# 1ChAmp_circuit_Large.net
KiCad netlist of a schematic drawn in EAGLE
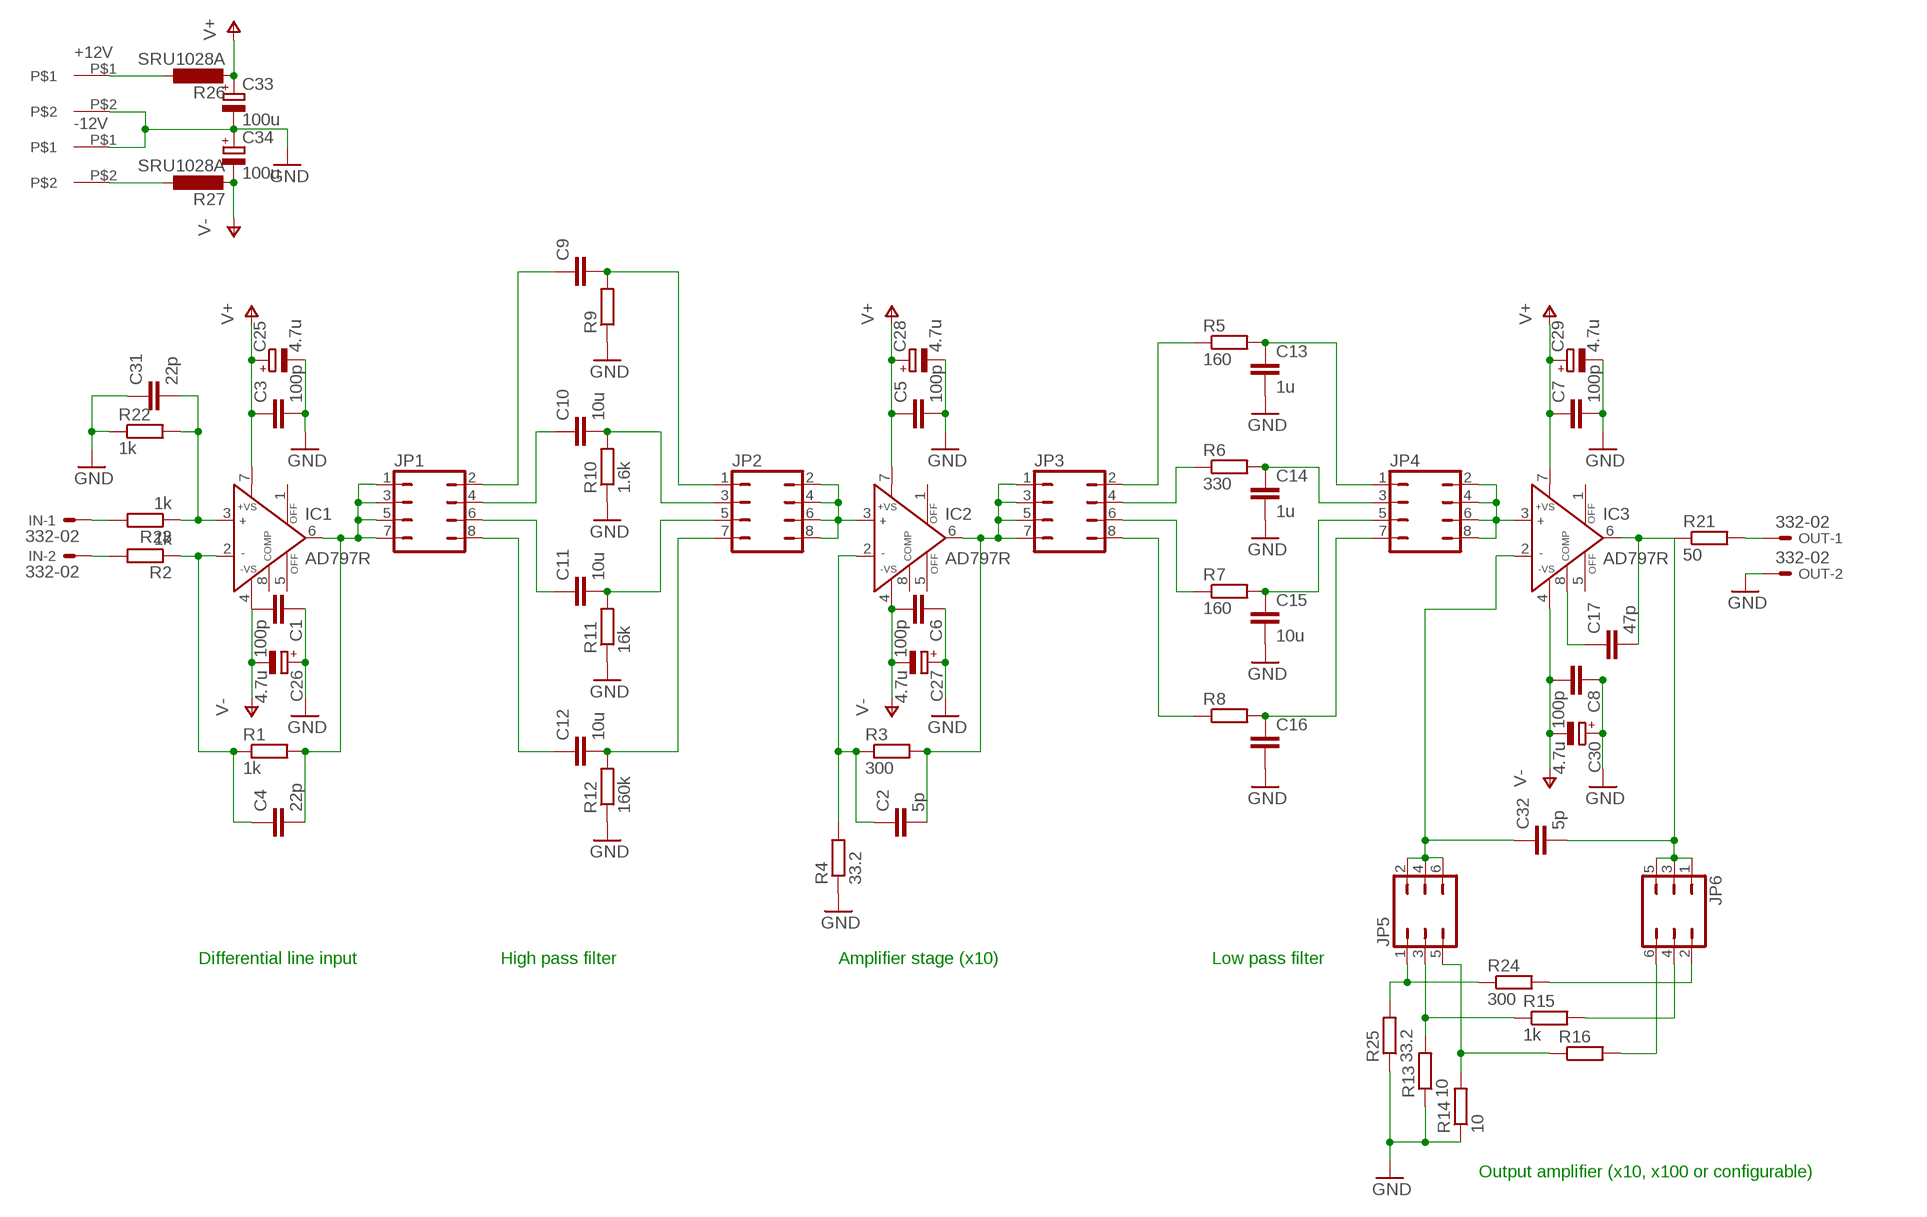
[diagram p0: schematic, sheet 1]

(export (version "E")
  (design (tool "Eeschema 10.0.6"))
  (components
    (comp (ref "+12V")
      (value "B2P-VH")
      (footprint "eagle-import:B2P-VH")
      (libsource (lib "eagle-import") (part "B2P-VH"))
    )
    (comp (ref "-12V")
      (value "B2P-VH")
      (footprint "eagle-import:B2P-VH")
      (libsource (lib "eagle-import") (part "B2P-VH"))
    )
    (comp (ref "C1")
      (value "100p")
      (footprint "eagle-import:C0805")
      (libsource (lib "eagle-import") (part "C-EUC0805"))
    )
    (comp (ref "C2")
      (value "5p")
      (footprint "eagle-import:C0805")
      (libsource (lib "eagle-import") (part "C-EUC0805"))
    )
    (comp (ref "C3")
      (value "100p")
      (footprint "eagle-import:C0805")
      (libsource (lib "eagle-import") (part "C-EUC0805"))
    )
    (comp (ref "C4")
      (value "22p")
      (footprint "eagle-import:C0805")
      (libsource (lib "eagle-import") (part "C-EUC0805"))
    )
    (comp (ref "C5")
      (value "100p")
      (footprint "eagle-import:C0805")
      (libsource (lib "eagle-import") (part "C-EUC0805"))
    )
    (comp (ref "C6")
      (value "100p")
      (footprint "eagle-import:C0805")
      (libsource (lib "eagle-import") (part "C-EUC0805"))
    )
    (comp (ref "C7")
      (value "100p")
      (footprint "eagle-import:C0805")
      (libsource (lib "eagle-import") (part "C-EUC0805"))
    )
    (comp (ref "C8")
      (value "100p")
      (footprint "eagle-import:C0805")
      (libsource (lib "eagle-import") (part "C-EUC0805"))
    )
    (comp (ref "C9")
      (value "C-EU025-025X050")
      (footprint "eagle-import:C025-025X050")
      (libsource (lib "eagle-import") (part "C-EU025-025X050"))
    )
    (comp (ref "C10")
      (value "10u")
      (footprint "eagle-import:C0805")
      (libsource (lib "eagle-import") (part "C-EUC0805"))
    )
    (comp (ref "C11")
      (value "10u")
      (footprint "eagle-import:C0805")
      (libsource (lib "eagle-import") (part "C-EUC0805"))
    )
    (comp (ref "C12")
      (value "10u")
      (footprint "eagle-import:C0805")
      (libsource (lib "eagle-import") (part "C-EUC0805"))
    )
    (comp (ref "C13")
      (value "1u")
      (footprint "eagle-import:C0805")
      (libsource (lib "eagle-import") (part "C-EUC0805"))
    )
    (comp (ref "C14")
      (value "1u")
      (footprint "eagle-import:C0805")
      (libsource (lib "eagle-import") (part "C-EUC0805"))
    )
    (comp (ref "C15")
      (value "10u")
      (footprint "eagle-import:C0805")
      (libsource (lib "eagle-import") (part "C-EUC0805"))
    )
    (comp (ref "C16")
      (value "C-EU025-025X050")
      (footprint "eagle-import:C025-025X050")
      (libsource (lib "eagle-import") (part "C-EU025-025X050"))
    )
    (comp (ref "C17")
      (value "47p")
      (footprint "eagle-import:C0805")
      (libsource (lib "eagle-import") (part "C-EUC0805"))
    )
    (comp (ref "C25")
      (value "4.7u")
      (footprint "eagle-import:C0805POL")
      (libsource (lib "eagle-import") (part "CPOL-EU"))
    )
    (comp (ref "C26")
      (value "4.7u")
      (footprint "eagle-import:C0805POL")
      (libsource (lib "eagle-import") (part "CPOL-EU"))
    )
    (comp (ref "C27")
      (value "4.7u")
      (footprint "eagle-import:C0805POL")
      (libsource (lib "eagle-import") (part "CPOL-EU"))
    )
    (comp (ref "C28")
      (value "4.7u")
      (footprint "eagle-import:C0805POL")
      (libsource (lib "eagle-import") (part "CPOL-EU"))
    )
    (comp (ref "C29")
      (value "4.7u")
      (footprint "eagle-import:C0805POL")
      (libsource (lib "eagle-import") (part "CPOL-EU"))
    )
    (comp (ref "C30")
      (value "4.7u")
      (footprint "eagle-import:C0805POL")
      (libsource (lib "eagle-import") (part "CPOL-EU"))
    )
    (comp (ref "C31")
      (value "22p")
      (footprint "eagle-import:C0805")
      (libsource (lib "eagle-import") (part "C-EUC0805"))
    )
    (comp (ref "C32")
      (value "5p")
      (footprint "eagle-import:C0805")
      (libsource (lib "eagle-import") (part "C-EUC0805"))
    )
    (comp (ref "C33")
      (value "100u")
      (footprint "eagle-import:C0805POL")
      (libsource (lib "eagle-import") (part "CPOL-EU"))
    )
    (comp (ref "C34")
      (value "100u")
      (footprint "eagle-import:C0805POL")
      (libsource (lib "eagle-import") (part "CPOL-EU"))
    )
    (comp (ref "IC1")
      (value "AD797R")
      (footprint "eagle-import:SO8")
      (fields (field (name "MF") "ALTERA CORPORATION") (field (name "MPN") "AD797ARZ"))
      (libsource (lib "eagle-import") (part "AD797R"))
    )
    (comp (ref "IC2")
      (value "AD797R")
      (footprint "eagle-import:SO8")
      (fields (field (name "MF") "ALTERA CORPORATION") (field (name "MPN") "AD797ARZ"))
      (libsource (lib "eagle-import") (part "AD797R"))
    )
    (comp (ref "IC3")
      (value "AD797R")
      (footprint "eagle-import:SO8")
      (fields (field (name "MF") "ALTERA CORPORATION") (field (name "MPN") "AD797ARZ"))
      (libsource (lib "eagle-import") (part "AD797R"))
    )
    (comp (ref "IN")
      (value "332-02")
      (footprint "eagle-import:332-02")
      (libsource (lib "eagle-import") (part "332-02"))
    )
    (comp (ref "JP1")
      (value "JP4Q")
      (footprint "eagle-import:JP4Q")
      (libsource (lib "eagle-import") (part "JP4Q"))
    )
    (comp (ref "JP2")
      (value "JP4Q")
      (footprint "eagle-import:JP4Q")
      (libsource (lib "eagle-import") (part "JP4Q"))
    )
    (comp (ref "JP3")
      (value "JP4Q")
      (footprint "eagle-import:JP4Q")
      (libsource (lib "eagle-import") (part "JP4Q"))
    )
    (comp (ref "JP4")
      (value "JP4Q")
      (footprint "eagle-import:JP4Q")
      (libsource (lib "eagle-import") (part "JP4Q"))
    )
    (comp (ref "JP5")
      (value "JP3Q")
      (footprint "eagle-import:JP3Q")
      (libsource (lib "eagle-import") (part "JP3Q"))
    )
    (comp (ref "JP6")
      (value "JP3Q")
      (footprint "eagle-import:JP3Q")
      (libsource (lib "eagle-import") (part "JP3Q"))
    )
    (comp (ref "OUT")
      (value "332-02")
      (footprint "eagle-import:332-02")
      (libsource (lib "eagle-import") (part "332-02"))
    )
    (comp (ref "R1")
      (value "1k")
      (footprint "eagle-import:R0805")
      (libsource (lib "eagle-import") (part "R-EU_R0805"))
    )
    (comp (ref "R2")
      (value "1k")
      (footprint "eagle-import:R0805")
      (libsource (lib "eagle-import") (part "R-EU_R0805"))
    )
    (comp (ref "R3")
      (value "300")
      (footprint "eagle-import:R0805")
      (libsource (lib "eagle-import") (part "R-EU_R0805"))
    )
    (comp (ref "R4")
      (value "33.2")
      (footprint "eagle-import:R0805")
      (libsource (lib "eagle-import") (part "R-EU_R0805"))
    )
    (comp (ref "R5")
      (value "160")
      (footprint "eagle-import:R0805")
      (libsource (lib "eagle-import") (part "R-EU_R0805"))
    )
    (comp (ref "R6")
      (value "330")
      (footprint "eagle-import:R0805")
      (libsource (lib "eagle-import") (part "R-EU_R0805"))
    )
    (comp (ref "R7")
      (value "160")
      (footprint "eagle-import:R0805")
      (libsource (lib "eagle-import") (part "R-EU_R0805"))
    )
    (comp (ref "R8")
      (value "R-EU_0204/5")
      (footprint "eagle-import:0204_5")
      (libsource (lib "eagle-import") (part "resistor_R-EU_0204/5"))
    )
    (comp (ref "R9")
      (value "R-EU_0204/5")
      (footprint "eagle-import:0204_5")
      (libsource (lib "eagle-import") (part "R-EU_0204/5"))
    )
    (comp (ref "R10")
      (value "1.6k")
      (footprint "eagle-import:R0805")
      (libsource (lib "eagle-import") (part "R-EU_R0805"))
    )
    (comp (ref "R11")
      (value "16k")
      (footprint "eagle-import:R0805")
      (libsource (lib "eagle-import") (part "R-EU_R0805"))
    )
    (comp (ref "R12")
      (value "160k")
      (footprint "eagle-import:R0805")
      (libsource (lib "eagle-import") (part "R-EU_R0805"))
    )
    (comp (ref "R13")
      (value "10")
      (footprint "eagle-import:R0805")
      (libsource (lib "eagle-import") (part "R-EU_R0805"))
    )
    (comp (ref "R14")
      (value "10")
      (footprint "eagle-import:R0805")
      (libsource (lib "eagle-import") (part "R-EU_R0805"))
    )
    (comp (ref "R15")
      (value "1k")
      (footprint "eagle-import:R0805")
      (libsource (lib "eagle-import") (part "R-EU_R0805"))
    )
    (comp (ref "R16")
      (value "R-EU_0204/5")
      (footprint "eagle-import:0204_5")
      (libsource (lib "eagle-import") (part "R-EU_0204/5"))
    )
    (comp (ref "R21")
      (value "50")
      (footprint "eagle-import:0204_5")
      (libsource (lib "eagle-import") (part "R-EU_0204/5"))
    )
    (comp (ref "R22")
      (value "1k")
      (footprint "eagle-import:R0805")
      (libsource (lib "eagle-import") (part "R-EU_R0805"))
    )
    (comp (ref "R23")
      (value "1k")
      (footprint "eagle-import:R0805")
      (libsource (lib "eagle-import") (part "R-EU_R0805"))
    )
    (comp (ref "R24")
      (value "300")
      (footprint "eagle-import:R0805")
      (libsource (lib "eagle-import") (part "R-EU_R0805"))
    )
    (comp (ref "R25")
      (value "33.2")
      (footprint "eagle-import:R0805")
      (libsource (lib "eagle-import") (part "R-EU_R0805"))
    )
    (comp (ref "R26")
      (value "SRU1028A")
      (footprint "eagle-import:SRU1028A")
      (libsource (lib "eagle-import") (part "SRU1028A"))
    )
    (comp (ref "R27")
      (value "SRU1028A")
      (footprint "eagle-import:SRU1028A")
      (libsource (lib "eagle-import") (part "SRU1028A"))
    )
  )
  (nets
    (net (code "1") (name "GND") (class "Default")
      (node (ref "+12V") (pin "P$2") (pinfunction "P$2_P$2") (pintype "bidirectional"))
      (node (ref "-12V") (pin "P$1") (pinfunction "P$1_P$1") (pintype "bidirectional"))
      (node (ref "C1") (pin "1") (pinfunction "1_1") (pintype "passive"))
      (node (ref "C13") (pin "2") (pinfunction "2_2") (pintype "passive"))
      (node (ref "C14") (pin "2") (pinfunction "2_2") (pintype "passive"))
      (node (ref "C15") (pin "2") (pinfunction "2_2") (pintype "passive"))
      (node (ref "C16") (pin "2") (pinfunction "2_2") (pintype "passive"))
      (node (ref "C25") (pin "P$1") (pinfunction "-_P$1") (pintype "passive"))
      (node (ref "C26") (pin "P$2") (pinfunction "+_P$2") (pintype "passive"))
      (node (ref "C27") (pin "P$2") (pinfunction "+_P$2") (pintype "passive"))
      (node (ref "C28") (pin "P$1") (pinfunction "-_P$1") (pintype "passive"))
      (node (ref "C29") (pin "P$1") (pinfunction "-_P$1") (pintype "passive"))
      (node (ref "C3") (pin "2") (pinfunction "2_2") (pintype "passive"))
      (node (ref "C30") (pin "P$2") (pinfunction "+_P$2") (pintype "passive"))
      (node (ref "C31") (pin "1") (pinfunction "1_1") (pintype "passive"))
      (node (ref "C33") (pin "P$1") (pinfunction "-_P$1") (pintype "passive"))
      (node (ref "C34") (pin "P$2") (pinfunction "+_P$2") (pintype "passive"))
      (node (ref "C5") (pin "2") (pinfunction "2_2") (pintype "passive"))
      (node (ref "C6") (pin "1") (pinfunction "1_1") (pintype "passive"))
      (node (ref "C7") (pin "2") (pinfunction "2_2") (pintype "passive"))
      (node (ref "C8") (pin "1") (pinfunction "1_1") (pintype "passive"))
      (node (ref "OUT") (pin "2") (pinfunction "S_2") (pintype "passive"))
      (node (ref "R10") (pin "1") (pinfunction "1_1") (pintype "passive"))
      (node (ref "R11") (pin "1") (pinfunction "1_1") (pintype "passive"))
      (node (ref "R12") (pin "1") (pinfunction "1_1") (pintype "passive"))
      (node (ref "R13") (pin "1") (pinfunction "1_1") (pintype "passive"))
      (node (ref "R14") (pin "1") (pinfunction "1_1") (pintype "passive"))
      (node (ref "R22") (pin "1") (pinfunction "1_1") (pintype "passive"))
      (node (ref "R25") (pin "1") (pinfunction "1_1") (pintype "passive"))
      (node (ref "R4") (pin "1") (pinfunction "1_1") (pintype "passive"))
      (node (ref "R9") (pin "1") (pinfunction "1_1") (pintype "passive"))
    )
    (net (code "2") (name "Net-(C9-Pad1)") (class "Default")
      (node (ref "C9") (pin "1") (pinfunction "1_1") (pintype "passive"))
      (node (ref "JP1") (pin "2") (pinfunction "2_2") (pintype "passive"))
    )
    (net (code "3") (name "Net-(C9-Pad2)") (class "Default")
      (node (ref "C9") (pin "2") (pinfunction "2_2") (pintype "passive"))
      (node (ref "JP2") (pin "1") (pinfunction "1_1") (pintype "passive"))
      (node (ref "R9") (pin "2") (pinfunction "2_2") (pintype "passive"))
    )
    (net (code "4") (name "Net-(C10-Pad1)") (class "Default")
      (node (ref "C10") (pin "1") (pinfunction "1_1") (pintype "passive"))
      (node (ref "JP1") (pin "4") (pinfunction "4_4") (pintype "passive"))
    )
    (net (code "5") (name "Net-(C10-Pad2)") (class "Default")
      (node (ref "C10") (pin "2") (pinfunction "2_2") (pintype "passive"))
      (node (ref "JP2") (pin "3") (pinfunction "3_3") (pintype "passive"))
      (node (ref "R10") (pin "2") (pinfunction "2_2") (pintype "passive"))
    )
    (net (code "6") (name "Net-(C11-Pad1)") (class "Default")
      (node (ref "C11") (pin "1") (pinfunction "1_1") (pintype "passive"))
      (node (ref "JP1") (pin "6") (pinfunction "6_6") (pintype "passive"))
    )
    (net (code "7") (name "Net-(C11-Pad2)") (class "Default")
      (node (ref "C11") (pin "2") (pinfunction "2_2") (pintype "passive"))
      (node (ref "JP2") (pin "5") (pinfunction "5_5") (pintype "passive"))
      (node (ref "R11") (pin "2") (pinfunction "2_2") (pintype "passive"))
    )
    (net (code "8") (name "Net-(C12-Pad1)") (class "Default")
      (node (ref "C12") (pin "1") (pinfunction "1_1") (pintype "passive"))
      (node (ref "JP1") (pin "8") (pinfunction "8_8") (pintype "passive"))
    )
    (net (code "9") (name "Net-(C12-Pad2)") (class "Default")
      (node (ref "C12") (pin "2") (pinfunction "2_2") (pintype "passive"))
      (node (ref "JP2") (pin "7") (pinfunction "7_7") (pintype "passive"))
      (node (ref "R12") (pin "2") (pinfunction "2_2") (pintype "passive"))
    )
    (net (code "10") (name "Net-(C13-Pad1)") (class "Default")
      (node (ref "C13") (pin "1") (pinfunction "1_1") (pintype "passive"))
      (node (ref "JP4") (pin "1") (pinfunction "1_1") (pintype "passive"))
      (node (ref "R5") (pin "2") (pinfunction "2_2") (pintype "passive"))
    )
    (net (code "11") (name "Net-(C14-Pad1)") (class "Default")
      (node (ref "C14") (pin "1") (pinfunction "1_1") (pintype "passive"))
      (node (ref "JP4") (pin "3") (pinfunction "3_3") (pintype "passive"))
      (node (ref "R6") (pin "2") (pinfunction "2_2") (pintype "passive"))
    )
    (net (code "12") (name "Net-(C15-Pad1)") (class "Default")
      (node (ref "C15") (pin "1") (pinfunction "1_1") (pintype "passive"))
      (node (ref "JP4") (pin "5") (pinfunction "5_5") (pintype "passive"))
      (node (ref "R7") (pin "2") (pinfunction "2_2") (pintype "passive"))
    )
    (net (code "13") (name "Net-(C16-Pad1)") (class "Default")
      (node (ref "C16") (pin "1") (pinfunction "1_1") (pintype "passive"))
      (node (ref "JP4") (pin "7") (pinfunction "7_7") (pintype "passive"))
      (node (ref "R8") (pin "2") (pinfunction "2_2") (pintype "passive"))
    )
    (net (code "14") (name "Net-(IC1-IN+)") (class "Default")
      (node (ref "C31") (pin "2") (pinfunction "2_2") (pintype "passive"))
      (node (ref "IC1") (pin "3") (pinfunction "IN+_3") (pintype "input"))
      (node (ref "R22") (pin "2") (pinfunction "2_2") (pintype "passive"))
      (node (ref "R23") (pin "1") (pinfunction "1_1") (pintype "passive"))
    )
    (net (code "15") (name "Net-(IC1-IN-)") (class "Default")
      (node (ref "C4") (pin "1") (pinfunction "1_1") (pintype "passive"))
      (node (ref "IC1") (pin "2") (pinfunction "IN-_2") (pintype "input"))
      (node (ref "R1") (pin "1") (pinfunction "1_1") (pintype "passive"))
      (node (ref "R2") (pin "1") (pinfunction "1_1") (pintype "passive"))
    )
    (net (code "16") (name "Net-(IC1-OUT)") (class "Default")
      (node (ref "C4") (pin "2") (pinfunction "2_2") (pintype "passive"))
      (node (ref "IC1") (pin "6") (pinfunction "OUT_6") (pintype "output"))
      (node (ref "JP1") (pin "1") (pinfunction "1_1") (pintype "passive"))
      (node (ref "JP1") (pin "3") (pinfunction "3_3") (pintype "passive"))
      (node (ref "JP1") (pin "5") (pinfunction "5_5") (pintype "passive"))
      (node (ref "JP1") (pin "7") (pinfunction "7_7") (pintype "passive"))
      (node (ref "R1") (pin "2") (pinfunction "2_2") (pintype "passive"))
    )
    (net (code "17") (name "Net-(IC2-IN+)") (class "Default")
      (node (ref "IC2") (pin "3") (pinfunction "IN+_3") (pintype "input"))
      (node (ref "JP2") (pin "2") (pinfunction "2_2") (pintype "passive"))
      (node (ref "JP2") (pin "4") (pinfunction "4_4") (pintype "passive"))
      (node (ref "JP2") (pin "6") (pinfunction "6_6") (pintype "passive"))
      (node (ref "JP2") (pin "8") (pinfunction "8_8") (pintype "passive"))
    )
    (net (code "18") (name "Net-(IC2-IN-)") (class "Default")
      (node (ref "C2") (pin "1") (pinfunction "1_1") (pintype "passive"))
      (node (ref "IC2") (pin "2") (pinfunction "IN-_2") (pintype "input"))
      (node (ref "R3") (pin "1") (pinfunction "1_1") (pintype "passive"))
      (node (ref "R4") (pin "2") (pinfunction "2_2") (pintype "passive"))
    )
    (net (code "19") (name "Net-(IC2-OUT)") (class "Default")
      (node (ref "C2") (pin "2") (pinfunction "2_2") (pintype "passive"))
      (node (ref "IC2") (pin "6") (pinfunction "OUT_6") (pintype "output"))
      (node (ref "JP3") (pin "1") (pinfunction "1_1") (pintype "passive"))
      (node (ref "JP3") (pin "3") (pinfunction "3_3") (pintype "passive"))
      (node (ref "JP3") (pin "5") (pinfunction "5_5") (pintype "passive"))
      (node (ref "JP3") (pin "7") (pinfunction "7_7") (pintype "passive"))
      (node (ref "R3") (pin "2") (pinfunction "2_2") (pintype "passive"))
    )
    (net (code "20") (name "Net-(IC3-COMP)") (class "Default")
      (node (ref "C17") (pin "1") (pinfunction "1_1") (pintype "passive"))
      (node (ref "IC3") (pin "8") (pinfunction "COMP_8") (pintype "passive"))
    )
    (net (code "21") (name "Net-(IC3-IN+)") (class "Default")
      (node (ref "IC3") (pin "3") (pinfunction "IN+_3") (pintype "input"))
      (node (ref "JP4") (pin "2") (pinfunction "2_2") (pintype "passive"))
      (node (ref "JP4") (pin "4") (pinfunction "4_4") (pintype "passive"))
      (node (ref "JP4") (pin "6") (pinfunction "6_6") (pintype "passive"))
      (node (ref "JP4") (pin "8") (pinfunction "8_8") (pintype "passive"))
    )
    (net (code "22") (name "Net-(IC3-IN-)") (class "Default")
      (node (ref "C32") (pin "1") (pinfunction "1_1") (pintype "passive"))
      (node (ref "IC3") (pin "2") (pinfunction "IN-_2") (pintype "input"))
      (node (ref "JP5") (pin "2") (pinfunction "2_2") (pintype "passive"))
      (node (ref "JP5") (pin "4") (pinfunction "4_4") (pintype "passive"))
      (node (ref "JP5") (pin "6") (pinfunction "6_6") (pintype "passive"))
    )
    (net (code "23") (name "Net-(IC3-OUT)") (class "Default")
      (node (ref "C17") (pin "2") (pinfunction "2_2") (pintype "passive"))
      (node (ref "C32") (pin "2") (pinfunction "2_2") (pintype "passive"))
      (node (ref "IC3") (pin "6") (pinfunction "OUT_6") (pintype "output"))
      (node (ref "JP6") (pin "1") (pinfunction "1_1") (pintype "passive"))
      (node (ref "JP6") (pin "3") (pinfunction "3_3") (pintype "passive"))
      (node (ref "JP6") (pin "5") (pinfunction "5_5") (pintype "passive"))
      (node (ref "R21") (pin "1") (pinfunction "1_1") (pintype "passive"))
    )
    (net (code "24") (name "Net-(INA-S)") (class "Default")
      (node (ref "IN") (pin "1") (pinfunction "S_1") (pintype "passive"))
      (node (ref "R23") (pin "2") (pinfunction "2_2") (pintype "passive"))
    )
    (net (code "25") (name "Net-(INB-S)") (class "Default")
      (node (ref "IN") (pin "2") (pinfunction "S_2") (pintype "passive"))
      (node (ref "R2") (pin "2") (pinfunction "2_2") (pintype "passive"))
    )
    (net (code "26") (name "Net-(JP3-Pad2)") (class "Default")
      (node (ref "JP3") (pin "2") (pinfunction "2_2") (pintype "passive"))
      (node (ref "R5") (pin "1") (pinfunction "1_1") (pintype "passive"))
    )
    (net (code "27") (name "Net-(JP3-Pad4)") (class "Default")
      (node (ref "JP3") (pin "4") (pinfunction "4_4") (pintype "passive"))
      (node (ref "R6") (pin "1") (pinfunction "1_1") (pintype "passive"))
    )
    (net (code "28") (name "Net-(JP3-Pad6)") (class "Default")
      (node (ref "JP3") (pin "6") (pinfunction "6_6") (pintype "passive"))
      (node (ref "R7") (pin "1") (pinfunction "1_1") (pintype "passive"))
    )
    (net (code "29") (name "Net-(JP3-Pad8)") (class "Default")
      (node (ref "JP3") (pin "8") (pinfunction "8_8") (pintype "passive"))
      (node (ref "R8") (pin "1") (pinfunction "1_1") (pintype "passive"))
    )
    (net (code "30") (name "Net-(JP5-Pad1)") (class "Default")
      (node (ref "JP5") (pin "1") (pinfunction "1_1") (pintype "passive"))
      (node (ref "R24") (pin "1") (pinfunction "1_1") (pintype "passive"))
      (node (ref "R25") (pin "2") (pinfunction "2_2") (pintype "passive"))
    )
    (net (code "31") (name "Net-(JP5-Pad3)") (class "Default")
      (node (ref "JP5") (pin "3") (pinfunction "3_3") (pintype "passive"))
      (node (ref "R13") (pin "2") (pinfunction "2_2") (pintype "passive"))
      (node (ref "R15") (pin "1") (pinfunction "1_1") (pintype "passive"))
    )
    (net (code "32") (name "Net-(JP5-Pad5)") (class "Default")
      (node (ref "JP5") (pin "5") (pinfunction "5_5") (pintype "passive"))
      (node (ref "R14") (pin "2") (pinfunction "2_2") (pintype "passive"))
      (node (ref "R16") (pin "1") (pinfunction "1_1") (pintype "passive"))
    )
    (net (code "33") (name "Net-(JP6-Pad2)") (class "Default")
      (node (ref "JP6") (pin "2") (pinfunction "2_2") (pintype "passive"))
      (node (ref "R24") (pin "2") (pinfunction "2_2") (pintype "passive"))
    )
    (net (code "34") (name "Net-(JP6-Pad4)") (class "Default")
      (node (ref "JP6") (pin "4") (pinfunction "4_4") (pintype "passive"))
      (node (ref "R15") (pin "2") (pinfunction "2_2") (pintype "passive"))
    )
    (net (code "35") (name "Net-(JP6-Pad6)") (class "Default")
      (node (ref "JP6") (pin "6") (pinfunction "6_6") (pintype "passive"))
      (node (ref "R16") (pin "2") (pinfunction "2_2") (pintype "passive"))
    )
    (net (code "36") (name "Net-(OUTA-S)") (class "Default")
      (node (ref "OUT") (pin "1") (pinfunction "S_1") (pintype "passive"))
      (node (ref "R21") (pin "2") (pinfunction "2_2") (pintype "passive"))
    )
    (net (code "37") (name "Net-(R26-1)") (class "Default")
      (node (ref "+12V") (pin "P$1") (pinfunction "P$1_P$1") (pintype "bidirectional"))
      (node (ref "R26") (pin "P$1") (pinfunction "1_P$1") (pintype "passive"))
    )
    (net (code "38") (name "Net-(R27-1)") (class "Default")
      (node (ref "-12V") (pin "P$2") (pinfunction "P$2_P$2") (pintype "bidirectional"))
      (node (ref "R27") (pin "P$1") (pinfunction "1_P$1") (pintype "passive"))
    )
    (net (code "39") (name "V+") (class "Default")
      (node (ref "C25") (pin "P$2") (pinfunction "+_P$2") (pintype "passive"))
      (node (ref "C28") (pin "P$2") (pinfunction "+_P$2") (pintype "passive"))
      (node (ref "C29") (pin "P$2") (pinfunction "+_P$2") (pintype "passive"))
      (node (ref "C3") (pin "1") (pinfunction "1_1") (pintype "passive"))
      (node (ref "C33") (pin "P$2") (pinfunction "+_P$2") (pintype "passive"))
      (node (ref "C5") (pin "1") (pinfunction "1_1") (pintype "passive"))
      (node (ref "C7") (pin "1") (pinfunction "1_1") (pintype "passive"))
      (node (ref "IC1") (pin "7") (pinfunction "+VS_7") (pintype "input"))
      (node (ref "IC2") (pin "7") (pinfunction "+VS_7") (pintype "input"))
      (node (ref "IC3") (pin "7") (pinfunction "+VS_7") (pintype "input"))
      (node (ref "R26") (pin "P$2") (pinfunction "2_P$2") (pintype "passive"))
    )
    (net (code "40") (name "V-") (class "Default")
      (node (ref "C1") (pin "2") (pinfunction "2_2") (pintype "passive"))
      (node (ref "C26") (pin "P$1") (pinfunction "-_P$1") (pintype "passive"))
      (node (ref "C27") (pin "P$1") (pinfunction "-_P$1") (pintype "passive"))
      (node (ref "C30") (pin "P$1") (pinfunction "-_P$1") (pintype "passive"))
      (node (ref "C34") (pin "P$1") (pinfunction "-_P$1") (pintype "passive"))
      (node (ref "C6") (pin "2") (pinfunction "2_2") (pintype "passive"))
      (node (ref "C8") (pin "2") (pinfunction "2_2") (pintype "passive"))
      (node (ref "IC1") (pin "4") (pinfunction "-VS_4") (pintype "input"))
      (node (ref "IC2") (pin "4") (pinfunction "-VS_4") (pintype "input"))
      (node (ref "IC3") (pin "4") (pinfunction "-VS_4") (pintype "input"))
      (node (ref "R27") (pin "P$2") (pinfunction "2_P$2") (pintype "passive"))
    )
    (net (code "41") (name "unconnected-(IC1-COMP-Pad8)") (class "Default")
      (node (ref "IC1") (pin "8") (pinfunction "COMP_8") (pintype "passive"))
    )
    (net (code "42") (name "unconnected-(IC1-OFF-Pad1)") (class "Default")
      (node (ref "IC1") (pin "1") (pinfunction "OFF_1") (pintype "passive"))
    )
    (net (code "43") (name "unconnected-(IC1-OFF-Pad5)") (class "Default")
      (node (ref "IC1") (pin "5") (pinfunction "OFF_5") (pintype "passive"))
    )
    (net (code "44") (name "unconnected-(IC2-COMP-Pad8)") (class "Default")
      (node (ref "IC2") (pin "8") (pinfunction "COMP_8") (pintype "passive"))
    )
    (net (code "45") (name "unconnected-(IC2-OFF-Pad1)") (class "Default")
      (node (ref "IC2") (pin "1") (pinfunction "OFF_1") (pintype "passive"))
    )
    (net (code "46") (name "unconnected-(IC2-OFF-Pad5)") (class "Default")
      (node (ref "IC2") (pin "5") (pinfunction "OFF_5") (pintype "passive"))
    )
    (net (code "47") (name "unconnected-(IC3-OFF-Pad1)") (class "Default")
      (node (ref "IC3") (pin "1") (pinfunction "OFF_1") (pintype "passive"))
    )
    (net (code "48") (name "unconnected-(IC3-OFF-Pad5)") (class "Default")
      (node (ref "IC3") (pin "5") (pinfunction "OFF_5") (pintype "passive"))
    )
  )
)
